# Sheet1.net
KiCad netlist of a schematic drawn in Altium Designer
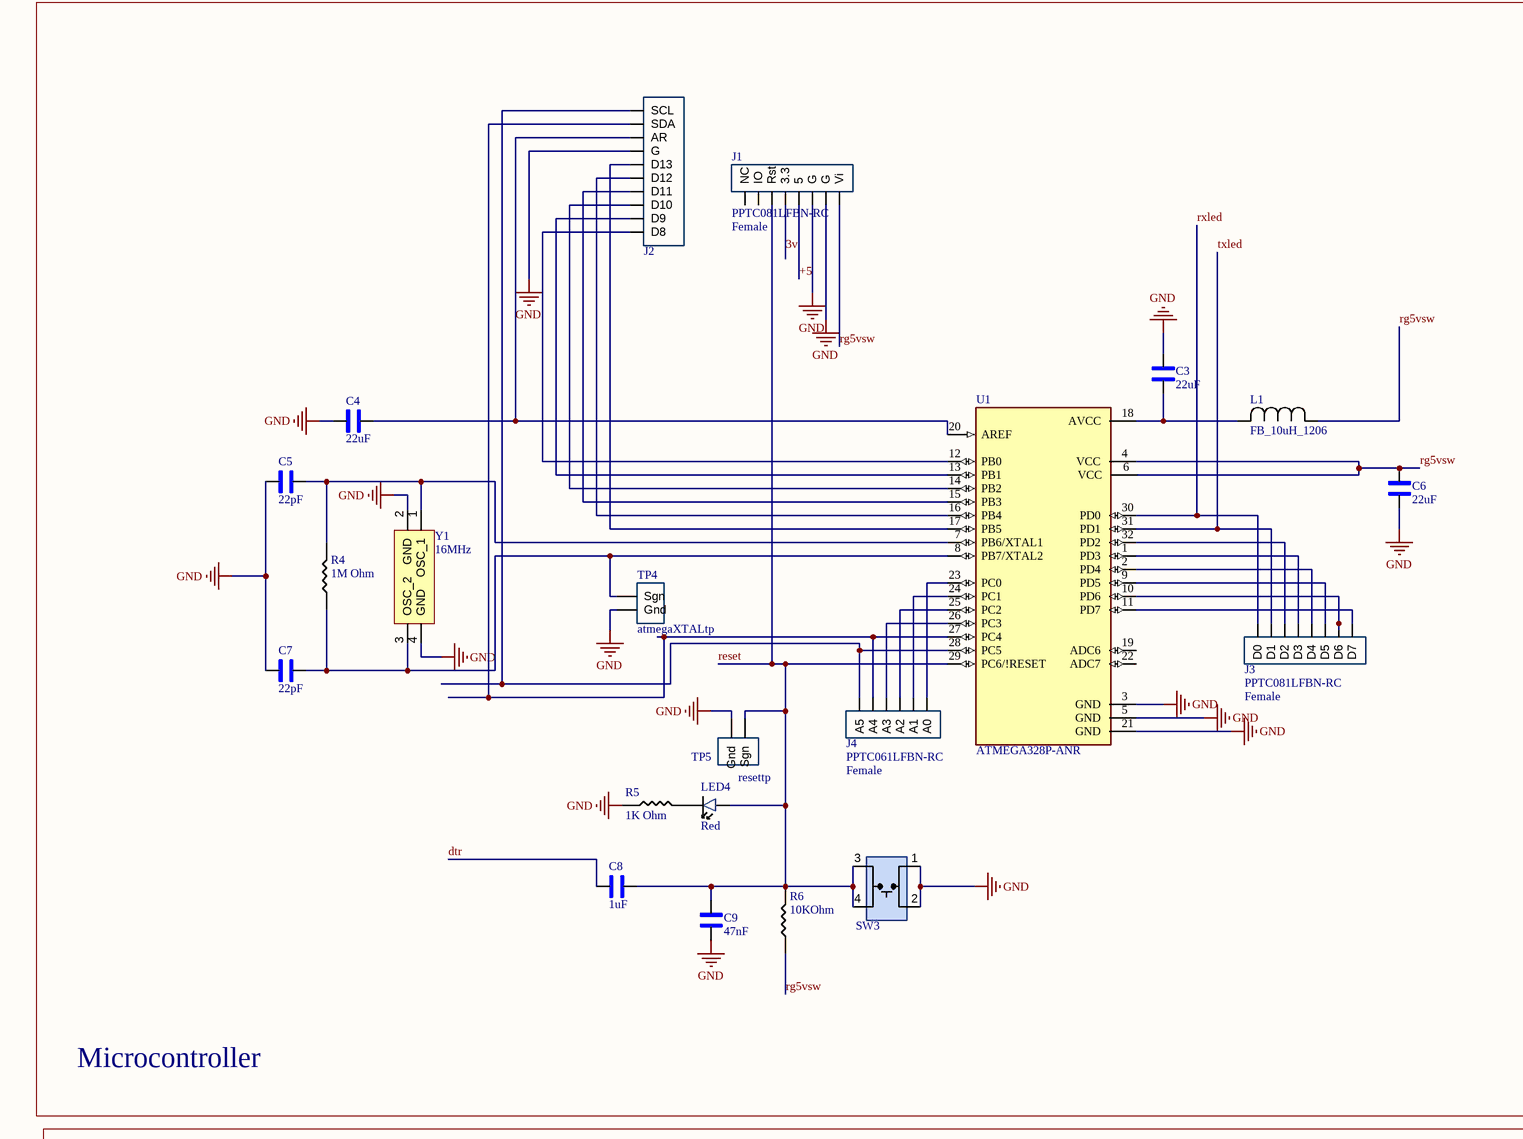
[diagram p0: Sheet1.SchDoc, top left]
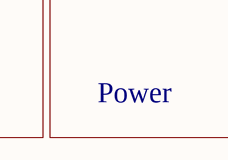
[diagram p1: Sheet1.SchDoc, top middle]
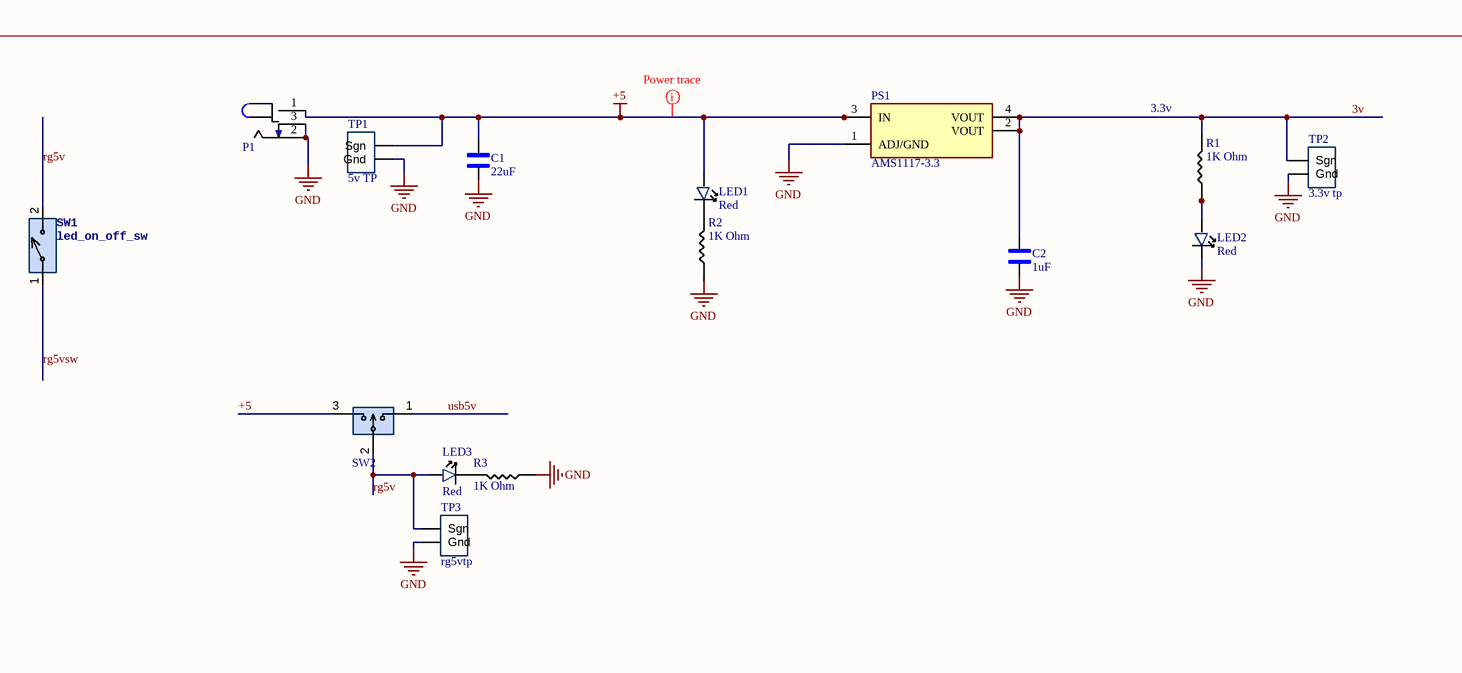
[diagram p2: Sheet1.SchDoc, top right]
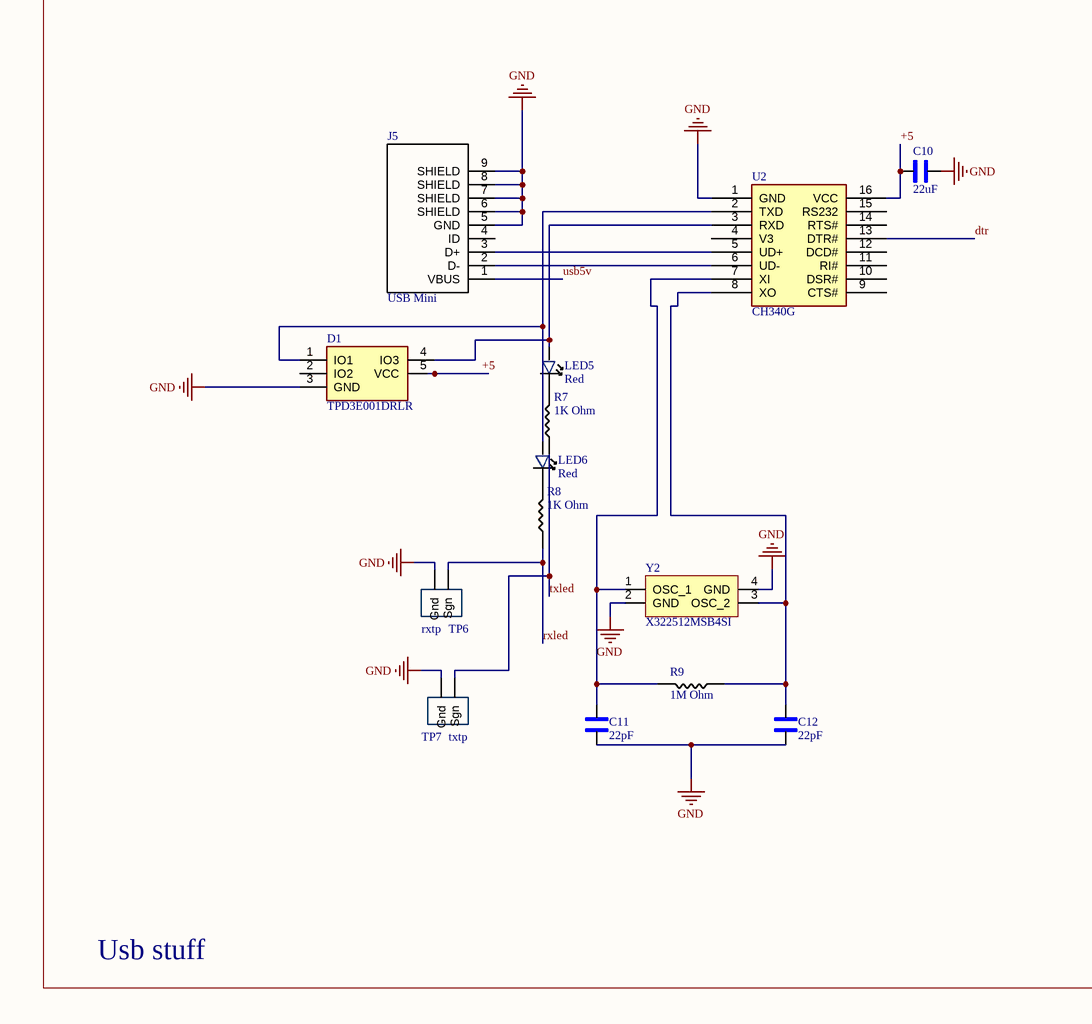
[diagram p3: Sheet1.SchDoc, bottom left]

(export (version "E")
  (design (tool "Eeschema 10.0.6"))
  (components
    (comp (ref "C1")
      (value "22uF")
      (footprint "1206_Passive_Capacitor")
      (description "22uF ±10% 25V X5R 1206 Multilayer Ceramic Capacitors MLCC - SMD/SMT RoHS")
      (fields (field (name "MFR PART #") "CL31A226KAHNNNE") (field (name "LCSC PART#") "C12891"))
      (libsource (lib "ECEN5730Lib_2023_05_DS") (part "C_22uF_1206"))
    )
    (comp (ref "C2")
      (value "1uF")
      (footprint "1206_Passive_Capacitor")
      (description "MULTILAYER CERAMIC CAPACITORS MLCC - SMD/SMT 1UF 50V 1206 ROHS")
      (fields (field (name "MFR PART #") "CL31B105KBHNNNE") (field (name "LCSC PART#") "C1848"))
      (libsource (lib "ECEN5730Lib_2023_05_DS") (part "C_1uF_1206"))
    )
    (comp (ref "C3")
      (value "22uF")
      (footprint "1206_Passive_Capacitor")
      (description "22uF ±10% 25V X5R 1206 Multilayer Ceramic Capacitors MLCC - SMD/SMT RoHS")
      (fields (field (name "MFR PART #") "CL31A226KAHNNNE") (field (name "LCSC PART#") "C12891"))
      (libsource (lib "ECEN5730Lib_2023_05_DS") (part "C_22uF_1206"))
    )
    (comp (ref "C4")
      (value "22uF")
      (footprint "1206_Passive_Capacitor")
      (description "22uF ±10% 25V X5R 1206 Multilayer Ceramic Capacitors MLCC - SMD/SMT RoHS")
      (fields (field (name "MFR PART #") "CL31A226KAHNNNE") (field (name "LCSC PART#") "C12891"))
      (libsource (lib "ECEN5730Lib_2023_05_DS") (part "C_22uF_1206"))
    )
    (comp (ref "C5")
      (value "22pF")
      (footprint "1206_Passive_Capacitor")
      (description "22pF ±5% 1kV C0G 1206 Multilayer Ceramic Capacitors MLCC - SMD/SMT RoHS")
      (fields (field (name "LCSC PART#") "C107174") (field (name "MFR PART #") "CC1206JKNPOCBN220"))
      (libsource (lib "ECEN5730Lib_2023_05_DS") (part "C_22pF_1206"))
    )
    (comp (ref "C6")
      (value "22uF")
      (footprint "1206_Passive_Capacitor")
      (description "22uF ±10% 25V X5R 1206 Multilayer Ceramic Capacitors MLCC - SMD/SMT RoHS")
      (fields (field (name "MFR PART #") "CL31A226KAHNNNE") (field (name "LCSC PART#") "C12891"))
      (libsource (lib "ECEN5730Lib_2023_05_DS") (part "C_22uF_1206"))
    )
    (comp (ref "C7")
      (value "22pF")
      (footprint "1206_Passive_Capacitor")
      (description "22pF ±5% 1kV C0G 1206 Multilayer Ceramic Capacitors MLCC - SMD/SMT RoHS")
      (fields (field (name "LCSC PART#") "C107174") (field (name "MFR PART #") "CC1206JKNPOCBN220"))
      (libsource (lib "ECEN5730Lib_2023_05_DS") (part "C_22pF_1206"))
    )
    (comp (ref "C8")
      (value "1uF")
      (footprint "1206_Passive_Capacitor")
      (description "MULTILAYER CERAMIC CAPACITORS MLCC - SMD/SMT 1UF 50V 1206 ROHS")
      (fields (field (name "MFR PART #") "CL31B105KBHNNNE") (field (name "LCSC PART#") "C1848"))
      (libsource (lib "ECEN5730Lib_2023_05_DS") (part "C_1uF_1206"))
    )
    (comp (ref "C9")
      (value "47nF")
      (footprint "1206_Passive_Capacitor")
      (description "47nF ±5% 50V C0G 1206 Multilayer Ceramic Capacitors MLCC - SMD/SMT RoHS")
      (fields (field (name "LCSC PART#") "C21812") (field (name "MFR PART #") "GRM31M5C1H473JA01L"))
      (libsource (lib "ECEN5730Lib_2023_05_DS") (part "C_47nF_1206"))
    )
    (comp (ref "C10")
      (value "22uF")
      (footprint "1206_Passive_Capacitor")
      (description "22uF ±10% 25V X5R 1206 Multilayer Ceramic Capacitors MLCC - SMD/SMT RoHS")
      (fields (field (name "MFR PART #") "CL31A226KAHNNNE") (field (name "LCSC PART#") "C12891"))
      (libsource (lib "ECEN5730Lib_2023_05_DS") (part "C_22uF_1206"))
    )
    (comp (ref "C11")
      (value "22pF")
      (footprint "1206_Passive_Capacitor")
      (description "22pF ±5% 1kV C0G 1206 Multilayer Ceramic Capacitors MLCC - SMD/SMT RoHS")
      (fields (field (name "LCSC PART#") "C107174") (field (name "MFR PART #") "CC1206JKNPOCBN220"))
      (libsource (lib "ECEN5730Lib_2023_05_DS") (part "C_22pF_1206"))
    )
    (comp (ref "C12")
      (value "22pF")
      (footprint "1206_Passive_Capacitor")
      (description "22pF ±5% 1kV C0G 1206 Multilayer Ceramic Capacitors MLCC - SMD/SMT RoHS")
      (fields (field (name "LCSC PART#") "C107174") (field (name "MFR PART #") "CC1206JKNPOCBN220"))
      (libsource (lib "ECEN5730Lib_2023_05_DS") (part "C_22pF_1206"))
    )
    (comp (ref "D1")
      (value "TPD3E001DRLR")
      (footprint "SOTFL50P160X60-5N:SOTFL50P160X60-5N")
      (description "Low-Capacitance 3-Channel +/-15KV ESD-Protection Array for High-Speed Data Interfaces")
      (fields (field (name "MOUSER PART NUMBER") "595-TPD3E001DRLR"))
      (libsource (lib "TPD3E001DRLR") (part "TPD3E001DRLR"))
    )
    (comp (ref "J1")
      (value "PPTC081LFBN-RC")
      (footprint "8_PIN_ARD-PWR_100MIL")
      (description "8 Position Header Connector 0.100\" (2.54mm) Through Hole Tin")
      (fields (field (name "LCSC PART#") "C27438") (field (name "ALTIUM_VALUE") "Female"))
      (libsource (lib "ECEN5730Lib_2023_05_DS") (part "JF_8_PIN_FEMA_ARD-Pwr"))
    )
    (comp (ref "J2")
      (value "PPTC101LFBN-RC")
      (footprint "10_PIN_ARDUINO_100MIL")
      (description "10 Position Header Connector 0.100\" (2.54mm) Through Hole Tin")
      (fields (field (name "LCSC PART#") "C225507"))
      (libsource (lib "ECEN5730Lib_2023_05_DS") (part "JF_10_PIN_FEMA_ARDUINO"))
    )
    (comp (ref "J3")
      (value "PPTC081LFBN-RC")
      (footprint "8_PIN_ARD-DIG_100MIL")
      (description "8 Position Header Connector 0.100\" (2.54mm) Through Hole Tin")
      (fields (field (name "LCSC PART#") "C27438") (field (name "ALTIUM_VALUE") "Female"))
      (libsource (lib "ECEN5730Lib_2023_05_DS") (part "JF_8_PIN_FEMA_ARD-Dig"))
    )
    (comp (ref "J4")
      (value "PPTC061LFBN-RC")
      (footprint "6_PIN_ARD-Analog_100mil")
      (description "6 Position Header Connector 0.100\" (2.54mm) Through Hole Tin")
      (fields (field (name "LCSC PART#") "C40877") (field (name "ALTIUM_VALUE") "Female"))
      (libsource (lib "ECEN5730Lib_2023_05_DS") (part "JF_6_PIN_FEMA_ARD-Anolog"))
    )
    (comp (ref "J5")
      (value "USB Mini")
      (footprint "USB_MINI_B")
      (description "Through Hole USB Connectors RoHS")
      (fields (field (name "LCSC PART#") "C46398") (field (name "MFR PART #") "920-462A2021D10102"))
      (libsource (lib "ECEN5730Lib_2023_05_DS") (part "J_USB_B_Mini"))
    )
    (comp (ref "L1")
      (value "FB_10uH_1206")
      (footprint "AIML-1206_ABR-M")
      (description "25mA 10uH ±10% 800mΩ 1206  Inductors (SMD) ROHS")
      (fields (field (name "MFR PART #") "CMI321609X100KT") (field (name "LCSC PART#") "C1051"))
      (libsource (lib "ECEN5730Lib_2023_05_DS") (part "FB_10uH_1206"))
    )
    (comp (ref "LED1")
      (value "Red")
      (footprint "LED_1206")
      (description "Red 621~631nm 1206 Light Emitting Diodes (LED) RoHS")
      (fields (field (name "MFR PART #") "15-21/R6C-FQ1R1B/2T") (field (name "LCSC PART#") "C93133"))
      (libsource (lib "ECEN5730Lib_2023_05_DS") (part "LED_RED_1206"))
    )
    (comp (ref "LED2")
      (value "Red")
      (footprint "LED_1206")
      (description "Red 621~631nm 1206 Light Emitting Diodes (LED) RoHS")
      (fields (field (name "MFR PART #") "15-21/R6C-FQ1R1B/2T") (field (name "LCSC PART#") "C93133"))
      (libsource (lib "ECEN5730Lib_2023_05_DS") (part "LED_RED_1206"))
    )
    (comp (ref "LED3")
      (value "Red")
      (footprint "LED_1206")
      (description "Red 621~631nm 1206 Light Emitting Diodes (LED) RoHS")
      (fields (field (name "MFR PART #") "15-21/R6C-FQ1R1B/2T") (field (name "LCSC PART#") "C93133"))
      (libsource (lib "ECEN5730Lib_2023_05_DS") (part "LED_RED_1206"))
    )
    (comp (ref "LED4")
      (value "Red")
      (footprint "LED_1206")
      (description "Red 621~631nm 1206 Light Emitting Diodes (LED) RoHS")
      (fields (field (name "MFR PART #") "15-21/R6C-FQ1R1B/2T") (field (name "LCSC PART#") "C93133"))
      (libsource (lib "ECEN5730Lib_2023_05_DS") (part "LED_RED_1206"))
    )
    (comp (ref "LED5")
      (value "Red")
      (footprint "LED_1206")
      (description "Red 621~631nm 1206 Light Emitting Diodes (LED) RoHS")
      (fields (field (name "MFR PART #") "15-21/R6C-FQ1R1B/2T") (field (name "LCSC PART#") "C93133"))
      (libsource (lib "ECEN5730Lib_2023_05_DS") (part "LED_RED_1206"))
    )
    (comp (ref "LED6")
      (value "Red")
      (footprint "LED_1206")
      (description "Red 621~631nm 1206 Light Emitting Diodes (LED) RoHS")
      (fields (field (name "MFR PART #") "15-21/R6C-FQ1R1B/2T") (field (name "LCSC PART#") "C93133"))
      (libsource (lib "ECEN5730Lib_2023_05_DS") (part "LED_RED_1206"))
    )
    (comp (ref "P1")
      (value "Power Jack")
      (footprint "Power_Jack")
      (description "Power Barrel Connector Jack 2.10mm ID (0.083\"), 5.50mm OD (0.217\") Through Hole, Right Angle")
      (fields (field (name "MFR PART #") "PJ-102A") (field (name "LCSC PART#") "C136744"))
      (libsource (lib "ECEN5730Lib_2023_05_DS") (part "P_Power Jack"))
    )
    (comp (ref "PS1")
      (value "AMS1117-3.3")
      (footprint "LDO")
      (description "LOW DROPOUT REGULATORS(LDO) POSITIVE FIXED 1.3V @ 800MA 15V 3.3V 1A SOT-223 ROHS")
      (fields (field (name "LCSC PART#") "C6186"))
      (libsource (lib "ECEN5730Lib_2023_05_DS") (part "PS_AMS_LDO_3v3"))
    )
    (comp (ref "R1")
      (value "1K Ohm")
      (footprint "1206_Passive_Resitor")
      (description "CHIP RESISTOR - SURFACE MOUNT 1KOHMS ±1% 1/4W 1206 ROHS")
      (fields (field (name "MFR PART #") "RNCP1206FTD1K00CT") (field (name "LCSC PART#") "C4410"))
      (libsource (lib "ECEN5730Lib_2023_05_DS") (part "R_1K_1206"))
    )
    (comp (ref "R2")
      (value "1K Ohm")
      (footprint "1206_Passive_Resitor")
      (description "CHIP RESISTOR - SURFACE MOUNT 1KOHMS ±1% 1/4W 1206 ROHS")
      (fields (field (name "MFR PART #") "RNCP1206FTD1K00CT") (field (name "LCSC PART#") "C4410"))
      (libsource (lib "ECEN5730Lib_2023_05_DS") (part "R_1K_1206"))
    )
    (comp (ref "R3")
      (value "1K Ohm")
      (footprint "1206_Passive_Resitor")
      (description "CHIP RESISTOR - SURFACE MOUNT 1KOHMS ±1% 1/4W 1206 ROHS")
      (fields (field (name "MFR PART #") "RNCP1206FTD1K00CT") (field (name "LCSC PART#") "C4410"))
      (libsource (lib "ECEN5730Lib_2023_05_DS") (part "R_1K_1206"))
    )
    (comp (ref "R4")
      (value "1M Ohm")
      (footprint "1206_Passive_Resitor")
      (description "CHIP RESISTOR - SURFACE MOUNT 1MOHMS ±1% 1/4W 1206 ROHS")
      (fields (field (name "MFR PART #") "RMCF1206JT1M00") (field (name "LCSC PART#") "C17927"))
      (libsource (lib "ECEN5730Lib_2023_05_DS") (part "R_1M_1206"))
    )
    (comp (ref "R5")
      (value "1K Ohm")
      (footprint "1206_Passive_Resitor")
      (description "CHIP RESISTOR - SURFACE MOUNT 1KOHMS ±1% 1/4W 1206 ROHS")
      (fields (field (name "MFR PART #") "RNCP1206FTD1K00CT") (field (name "LCSC PART#") "C4410"))
      (libsource (lib "ECEN5730Lib_2023_05_DS") (part "R_1K_1206"))
    )
    (comp (ref "R6")
      (value "10KOhm")
      (footprint "1206_Passive_Resitor")
      (description "10 kOhms ±5% 0.25W, 1/4W Chip Resistor 1206 (3216 Metric) Automotive AEC-Q200 Thick Film")
      (fields (field (name "MFR PART #") "RMCF1206FT10K0") (field (name "LCSC PART#") "C17902"))
      (libsource (lib "ECEN5730Lib_2023_05_DS") (part "R_10KOhm_1206"))
    )
    (comp (ref "R7")
      (value "1K Ohm")
      (footprint "1206_Passive_Resitor")
      (description "CHIP RESISTOR - SURFACE MOUNT 1KOHMS ±1% 1/4W 1206 ROHS")
      (fields (field (name "MFR PART #") "RNCP1206FTD1K00CT") (field (name "LCSC PART#") "C4410"))
      (libsource (lib "ECEN5730Lib_2023_05_DS") (part "R_1K_1206"))
    )
    (comp (ref "R8")
      (value "1K Ohm")
      (footprint "1206_Passive_Resitor")
      (description "CHIP RESISTOR - SURFACE MOUNT 1KOHMS ±1% 1/4W 1206 ROHS")
      (fields (field (name "MFR PART #") "RNCP1206FTD1K00CT") (field (name "LCSC PART#") "C4410"))
      (libsource (lib "ECEN5730Lib_2023_05_DS") (part "R_1K_1206"))
    )
    (comp (ref "R9")
      (value "1M Ohm")
      (footprint "1206_Passive_Resitor")
      (description "CHIP RESISTOR - SURFACE MOUNT 1MOHMS ±1% 1/4W 1206 ROHS")
      (fields (field (name "MFR PART #") "RMCF1206JT1M00") (field (name "LCSC PART#") "C17927"))
      (libsource (lib "ECEN5730Lib_2023_05_DS") (part "R_1M_1206"))
    )
    (comp (ref "SW1")
      (value "led_on_off_sw")
      (footprint "2Pin-Header-Conn")
      (description "2Pin Header")
      (fields (field (name "LCSC PART#") "C124375"))
      (libsource (lib "ECEN5730Lib_2023_05_DS") (part "SW_2Pin_100mil_Switch"))
    )
    (comp (ref "SW2")
      (value "PREC003SAAN-RC")
      (footprint "3_PIN_100mil")
      (description "Connector Header Through Hole 3 position 0.100\" (2.54mm)")
      (fields (field (name "LCSC PART#") "C49257"))
      (libsource (lib "ECEN5730Lib_2023_05_DS") (part "SW_3Pin_100mil_Switch"))
    )
    (comp (ref "SW3")
      (value "TL3305AF160QG")
      (footprint "Switch_JLC")
      (description "Tactile Switch SPST-NO Top Actuated Surface Mount")
      (fields (field (name "MFR PART #") "KH-4.5X4.5X4.3H-STM") (field (name "LCSC PART#") "C2837550"))
      (libsource (lib "ECEN5730Lib_2023_05_DS") (part "SW_Push_Button_JLC"))
    )
    (comp (ref "TP1")
      (value "5v TP")
      (footprint "TP10x_Probe")
      (description "Test Point 300 mil centers")
      (libsource (lib "ECEN5730Lib_2023_05_DS") (part "TP_10x_Probe"))
    )
    (comp (ref "TP2")
      (value "3.3v tp")
      (footprint "TP10x_Probe")
      (description "Test Point 300 mil centers")
      (libsource (lib "") (part "TP_10x_Probe_1"))
    )
    (comp (ref "TP3")
      (value "rg5vtp")
      (footprint "TP10x_Probe")
      (description "Test Point 300 mil centers")
      (libsource (lib "") (part "TP_10x_Probe_1"))
    )
    (comp (ref "TP4")
      (value "atmegaXTALtp")
      (footprint "TP10x_Probe")
      (description "Test Point 300 mil centers")
      (libsource (lib "") (part "TP_10x_Probe_1"))
    )
    (comp (ref "TP5")
      (value "resettp")
      (footprint "TP10x_Probe")
      (description "Test Point 300 mil centers")
      (libsource (lib "ECEN5730Lib_2023_05_DS") (part "TP_10x_Probe"))
    )
    (comp (ref "TP6")
      (value "rxtp")
      (footprint "TP10x_Probe")
      (description "Test Point 300 mil centers")
      (libsource (lib "ECEN5730Lib_2023_05_DS") (part "TP_10x_Probe"))
    )
    (comp (ref "TP7")
      (value "txtp")
      (footprint "TP10x_Probe")
      (description "Test Point 300 mil centers")
      (libsource (lib "ECEN5730Lib_2023_05_DS") (part "TP_10x_Probe"))
    )
    (comp (ref "U1")
      (value "ATMEGA328P-ANR")
      (footprint "ATMega328P")
      (description "AVR AVR® ATmega Microcontroller IC 8-Bit 20MHz 32KB (16K x 16) FLASH 32-TQFP (7x7)")
      (fields (field (name "MFR PART #") "ATMEGA328P-AU") (field (name "LCSC PART#") "C14877"))
      (libsource (lib "ECEN5730Lib_2023_05_DS") (part "U_ATMega328P"))
    )
    (comp (ref "U2")
      (value "CH340G")
      (footprint "USB to serial")
      (description "Transceiver USB 2.0 2Mbps SOP-16_150mil USB ICs RoHS")
      (fields (field (name "LCSC PART#") "C14267"))
      (libsource (lib "ECEN5730Lib_2023_05_DS") (part "U_USBtoSerial"))
    )
    (comp (ref "Y1")
      (value "16MHz")
      (footprint "Crystal resonator")
      (description "±10ppm 16000000Hz -40℃~85℃ 贴片无源晶振 60Ω 9pF SMD3225-4P Crystals ROHS")
      (fields (field (name "LCSC PART#") "C13738") (field (name "MFR PART #") "X322516MLB4SI"))
      (libsource (lib "ECEN5730Lib_2023_05_DS") (part "X_16Mhz_Res"))
    )
    (comp (ref "Y2")
      (value "X322512MSB4SI")
      (footprint "Crystal resonator")
      (description "SMD Crystal Resonators 12MHz ±10ppm SMD-3225_4P RoHS")
      (fields (field (name "LCSC PART#") "C9002"))
      (libsource (lib "ECEN5730Lib_2023_05_DS") (part "X_12MHz_Res"))
    )
  )
  (nets
    (net (code "1") (name "+5") (class "Default")
      (node (ref "C1") (pin "2") (pinfunction "2_2") (pintype "passive"))
      (node (ref "C10") (pin "1") (pinfunction "1_1") (pintype "passive"))
      (node (ref "D1") (pin "5") (pinfunction "VCC_5") (pintype "passive"))
      (node (ref "J1") (pin "5") (pinfunction "5_5") (pintype "passive"))
      (node (ref "LED1") (pin "1") (pinfunction "1_1") (pintype "passive"))
      (node (ref "P1") (pin "1") (pinfunction "1_1") (pintype "power_in"))
      (node (ref "PS1") (pin "3") (pinfunction "IN_3") (pintype "power_in"))
      (node (ref "SW2") (pin "3") (pinfunction "3_3") (pintype "passive"))
      (node (ref "TP1") (pin "1") (pinfunction "Sgn_1") (pintype "passive"))
      (node (ref "U2") (pin "16") (pinfunction "VCC_16") (pintype "passive"))
    )
    (net (code "2") (name "/3v") (class "Default")
      (node (ref "C2") (pin "2") (pinfunction "2_2") (pintype "passive"))
      (node (ref "J1") (pin "4") (pinfunction "3.3_4") (pintype "passive"))
      (node (ref "PS1") (pin "2") (pinfunction "VOUT_2") (pintype "power_in"))
      (node (ref "PS1") (pin "4") (pinfunction "VOUT_4") (pintype "power_in"))
      (node (ref "R1") (pin "2") (pinfunction "2_2") (pintype "passive"))
      (node (ref "TP2") (pin "1") (pinfunction "Sgn_1") (pintype "passive"))
    )
    (net (code "3") (name "/dtr") (class "Default")
      (node (ref "C8") (pin "1") (pinfunction "1_1") (pintype "passive"))
      (node (ref "U2") (pin "13") (pinfunction "DTR#_13") (pintype "passive"))
    )
    (net (code "4") (name "/reset") (class "Default")
      (node (ref "C8") (pin "2") (pinfunction "2_2") (pintype "passive"))
      (node (ref "C9") (pin "2") (pinfunction "2_2") (pintype "passive"))
      (node (ref "J1") (pin "3") (pinfunction "Rst_3") (pintype "passive"))
      (node (ref "LED4") (pin "1") (pinfunction "1_1") (pintype "passive"))
      (node (ref "R6") (pin "2") (pinfunction "2_2") (pintype "passive"))
      (node (ref "SW3") (pin "3") (pinfunction "3_3") (pintype "passive"))
      (node (ref "SW3") (pin "4") (pinfunction "4_4") (pintype "passive"))
      (node (ref "TP5") (pin "1") (pinfunction "Sgn_1") (pintype "passive"))
      (node (ref "U1") (pin "29") (pinfunction "PC6/!RESET_29") (pintype "bidirectional"))
    )
    (net (code "5") (name "/rg5v") (class "Default")
      (node (ref "LED3") (pin "1") (pinfunction "1_1") (pintype "passive"))
      (node (ref "SW1") (pin "2") (pinfunction "2_2") (pintype "passive"))
      (node (ref "SW2") (pin "2") (pinfunction "2_2") (pintype "passive"))
      (node (ref "TP3") (pin "1") (pinfunction "Sgn_1") (pintype "passive"))
    )
    (net (code "6") (name "/rg5vsw") (class "Default")
      (node (ref "C6") (pin "2") (pinfunction "2_2") (pintype "passive"))
      (node (ref "J1") (pin "8") (pinfunction "Vi_8") (pintype "passive"))
      (node (ref "L1") (pin "1") (pinfunction "1_1") (pintype "passive"))
      (node (ref "R6") (pin "1") (pinfunction "1_1") (pintype "passive"))
      (node (ref "SW1") (pin "1") (pinfunction "1_1") (pintype "passive"))
      (node (ref "U1") (pin "4") (pinfunction "VCC_4") (pintype "power_in"))
      (node (ref "U1") (pin "6") (pinfunction "VCC_6") (pintype "power_in"))
    )
    (net (code "7") (name "/rxled") (class "Default")
      (node (ref "J3") (pin "8") (pinfunction "D0_8") (pintype "passive"))
      (node (ref "R8") (pin "1") (pinfunction "1_1") (pintype "passive"))
      (node (ref "TP6") (pin "1") (pinfunction "Sgn_1") (pintype "passive"))
      (node (ref "U1") (pin "30") (pinfunction "PD0_30") (pintype "bidirectional"))
    )
    (net (code "8") (name "/txled") (class "Default")
      (node (ref "J3") (pin "7") (pinfunction "D1_7") (pintype "passive"))
      (node (ref "R7") (pin "1") (pinfunction "1_1") (pintype "passive"))
      (node (ref "TP7") (pin "1") (pinfunction "Sgn_1") (pintype "passive"))
      (node (ref "U1") (pin "31") (pinfunction "PD1_31") (pintype "bidirectional"))
    )
    (net (code "9") (name "/usb5v") (class "Default")
      (node (ref "J5") (pin "1") (pinfunction "VBUS_1") (pintype "passive"))
      (node (ref "SW2") (pin "1") (pinfunction "1_1") (pintype "passive"))
    )
    (net (code "10") (name "GND") (class "Default")
      (node (ref "C1") (pin "1") (pinfunction "1_1") (pintype "passive"))
      (node (ref "C10") (pin "2") (pinfunction "2_2") (pintype "passive"))
      (node (ref "C11") (pin "1") (pinfunction "1_1") (pintype "passive"))
      (node (ref "C12") (pin "1") (pinfunction "1_1") (pintype "passive"))
      (node (ref "C2") (pin "1") (pinfunction "1_1") (pintype "passive"))
      (node (ref "C3") (pin "2") (pinfunction "2_2") (pintype "passive"))
      (node (ref "C4") (pin "2") (pinfunction "2_2") (pintype "passive"))
      (node (ref "C5") (pin "1") (pinfunction "1_1") (pintype "passive"))
      (node (ref "C6") (pin "1") (pinfunction "1_1") (pintype "passive"))
      (node (ref "C7") (pin "1") (pinfunction "1_1") (pintype "passive"))
      (node (ref "C9") (pin "1") (pinfunction "1_1") (pintype "passive"))
      (node (ref "D1") (pin "3") (pinfunction "GND_3") (pintype "passive"))
      (node (ref "J1") (pin "6") (pinfunction "G_6") (pintype "passive"))
      (node (ref "J1") (pin "7") (pinfunction "G_7") (pintype "passive"))
      (node (ref "J2") (pin "4") (pinfunction "G_4") (pintype "passive"))
      (node (ref "J5") (pin "5") (pinfunction "GND_5") (pintype "passive"))
      (node (ref "J5") (pin "6") (pinfunction "SHIELD_6") (pintype "passive"))
      (node (ref "J5") (pin "7") (pinfunction "SHIELD_7") (pintype "passive"))
      (node (ref "J5") (pin "8") (pinfunction "SHIELD_8") (pintype "passive"))
      (node (ref "J5") (pin "9") (pinfunction "SHIELD_9") (pintype "passive"))
      (node (ref "LED2") (pin "2") (pinfunction "2_2") (pintype "passive"))
      (node (ref "P1") (pin "2") (pinfunction "2_2") (pintype "power_in"))
      (node (ref "P1") (pin "3") (pinfunction "3_3") (pintype "power_in"))
      (node (ref "PS1") (pin "1") (pinfunction "ADJ/GND_1") (pintype "passive"))
      (node (ref "R2") (pin "1") (pinfunction "1_1") (pintype "passive"))
      (node (ref "R3") (pin "1") (pinfunction "1_1") (pintype "passive"))
      (node (ref "R5") (pin "1") (pinfunction "1_1") (pintype "passive"))
      (node (ref "SW3") (pin "1") (pinfunction "1_1") (pintype "passive"))
      (node (ref "SW3") (pin "2") (pinfunction "2_2") (pintype "passive"))
      (node (ref "TP1") (pin "2") (pinfunction "Gnd_2") (pintype "passive"))
      (node (ref "TP2") (pin "2") (pinfunction "Gnd_2") (pintype "passive"))
      (node (ref "TP3") (pin "2") (pinfunction "Gnd_2") (pintype "passive"))
      (node (ref "TP4") (pin "2") (pinfunction "Gnd_2") (pintype "passive"))
      (node (ref "TP5") (pin "2") (pinfunction "Gnd_2") (pintype "passive"))
      (node (ref "TP6") (pin "2") (pinfunction "Gnd_2") (pintype "passive"))
      (node (ref "TP7") (pin "2") (pinfunction "Gnd_2") (pintype "passive"))
      (node (ref "U1") (pin "21") (pinfunction "GND_21") (pintype "power_in"))
      (node (ref "U1") (pin "3") (pinfunction "GND_3") (pintype "power_in"))
      (node (ref "U1") (pin "5") (pinfunction "GND_5") (pintype "power_in"))
      (node (ref "U2") (pin "1") (pinfunction "GND_1") (pintype "passive"))
      (node (ref "Y1") (pin "2") (pinfunction "GND_2") (pintype "passive"))
      (node (ref "Y1") (pin "4") (pinfunction "GND_4") (pintype "passive"))
      (node (ref "Y2") (pin "2") (pinfunction "GND_2") (pintype "passive"))
      (node (ref "Y2") (pin "4") (pinfunction "GND_4") (pintype "passive"))
    )
    (net (code "11") (name "Net-(D1-IO1)") (class "Default")
      (node (ref "D1") (pin "1") (pinfunction "IO1_1") (pintype "passive"))
      (node (ref "LED6") (pin "1") (pinfunction "1_1") (pintype "passive"))
      (node (ref "U2") (pin "2") (pinfunction "TXD_2") (pintype "passive"))
    )
    (net (code "12") (name "Net-(D1-IO3)") (class "Default")
      (node (ref "D1") (pin "4") (pinfunction "IO3_4") (pintype "passive"))
      (node (ref "LED5") (pin "1") (pinfunction "1_1") (pintype "passive"))
      (node (ref "U2") (pin "3") (pinfunction "RXD_3") (pintype "passive"))
    )
    (net (code "13") (name "Net-(J2-AR)") (class "Default")
      (node (ref "C4") (pin "1") (pinfunction "1_1") (pintype "passive"))
      (node (ref "J2") (pin "3") (pinfunction "AR_3") (pintype "passive"))
      (node (ref "U1") (pin "20") (pinfunction "AREF_20") (pintype "input"))
    )
    (net (code "14") (name "Net-(J2-D8)") (class "Default")
      (node (ref "J2") (pin "10") (pinfunction "D8_10") (pintype "passive"))
      (node (ref "U1") (pin "12") (pinfunction "PB0_12") (pintype "bidirectional"))
    )
    (net (code "15") (name "Net-(J2-D9)") (class "Default")
      (node (ref "J2") (pin "9") (pinfunction "D9_9") (pintype "passive"))
      (node (ref "U1") (pin "13") (pinfunction "PB1_13") (pintype "bidirectional"))
    )
    (net (code "16") (name "Net-(J2-D10)") (class "Default")
      (node (ref "J2") (pin "8") (pinfunction "D10_8") (pintype "passive"))
      (node (ref "U1") (pin "14") (pinfunction "PB2_14") (pintype "bidirectional"))
    )
    (net (code "17") (name "Net-(J2-D11)") (class "Default")
      (node (ref "J2") (pin "7") (pinfunction "D11_7") (pintype "passive"))
      (node (ref "U1") (pin "15") (pinfunction "PB3_15") (pintype "bidirectional"))
    )
    (net (code "18") (name "Net-(J2-D12)") (class "Default")
      (node (ref "J2") (pin "6") (pinfunction "D12_6") (pintype "passive"))
      (node (ref "U1") (pin "16") (pinfunction "PB4_16") (pintype "bidirectional"))
    )
    (net (code "19") (name "Net-(J2-D13)") (class "Default")
      (node (ref "J2") (pin "5") (pinfunction "D13_5") (pintype "passive"))
      (node (ref "U1") (pin "17") (pinfunction "PB5_17") (pintype "bidirectional"))
    )
    (net (code "20") (name "Net-(J2-SCL)") (class "Default")
      (node (ref "J2") (pin "1") (pinfunction "SCL_1") (pintype "passive"))
      (node (ref "J4") (pin "6") (pinfunction "A5_6") (pintype "passive"))
      (node (ref "U1") (pin "28") (pinfunction "PC5_28") (pintype "bidirectional"))
    )
    (net (code "21") (name "Net-(J2-SDA)") (class "Default")
      (node (ref "J2") (pin "2") (pinfunction "SDA_2") (pintype "passive"))
      (node (ref "J4") (pin "5") (pinfunction "A4_5") (pintype "passive"))
      (node (ref "U1") (pin "27") (pinfunction "PC4_27") (pintype "bidirectional"))
    )
    (net (code "22") (name "Net-(J3-D2)") (class "Default")
      (node (ref "J3") (pin "6") (pinfunction "D2_6") (pintype "passive"))
      (node (ref "U1") (pin "32") (pinfunction "PD2_32") (pintype "bidirectional"))
    )
    (net (code "23") (name "Net-(J3-D3)") (class "Default")
      (node (ref "J3") (pin "5") (pinfunction "D3_5") (pintype "passive"))
      (node (ref "U1") (pin "1") (pinfunction "PD3_1") (pintype "bidirectional"))
    )
    (net (code "24") (name "Net-(J3-D4)") (class "Default")
      (node (ref "J3") (pin "4") (pinfunction "D4_4") (pintype "passive"))
      (node (ref "U1") (pin "2") (pinfunction "PD4_2") (pintype "bidirectional"))
    )
    (net (code "25") (name "Net-(J3-D5)") (class "Default")
      (node (ref "J3") (pin "3") (pinfunction "D5_3") (pintype "passive"))
      (node (ref "U1") (pin "9") (pinfunction "PD5_9") (pintype "bidirectional"))
    )
    (net (code "26") (name "Net-(J3-D6)") (class "Default")
      (node (ref "J3") (pin "2") (pinfunction "D6_2") (pintype "passive"))
      (node (ref "U1") (pin "10") (pinfunction "PD6_10") (pintype "bidirectional"))
    )
    (net (code "27") (name "Net-(J3-D7)") (class "Default")
      (node (ref "J3") (pin "1") (pinfunction "D7_1") (pintype "passive"))
      (node (ref "U1") (pin "11") (pinfunction "PD7_11") (pintype "bidirectional"))
    )
    (net (code "28") (name "Net-(J4-A0)") (class "Default")
      (node (ref "J4") (pin "1") (pinfunction "A0_1") (pintype "passive"))
      (node (ref "U1") (pin "23") (pinfunction "PC0_23") (pintype "bidirectional"))
    )
    (net (code "29") (name "Net-(J4-A1)") (class "Default")
      (node (ref "J4") (pin "2") (pinfunction "A1_2") (pintype "passive"))
      (node (ref "U1") (pin "24") (pinfunction "PC1_24") (pintype "bidirectional"))
    )
    (net (code "30") (name "Net-(J4-A2)") (class "Default")
      (node (ref "J4") (pin "3") (pinfunction "A2_3") (pintype "passive"))
      (node (ref "U1") (pin "25") (pinfunction "PC2_25") (pintype "bidirectional"))
    )
    (net (code "31") (name "Net-(J4-A3)") (class "Default")
      (node (ref "J4") (pin "4") (pinfunction "A3_4") (pintype "passive"))
      (node (ref "U1") (pin "26") (pinfunction "PC3_26") (pintype "bidirectional"))
    )
    (net (code "32") (name "Net-(J5-D+)") (class "Default")
      (node (ref "J5") (pin "3") (pinfunction "D+_3") (pintype "passive"))
      (node (ref "U2") (pin "5") (pinfunction "UD+_5") (pintype "passive"))
    )
    (net (code "33") (name "Net-(J5-D-)") (class "Default")
      (node (ref "J5") (pin "2") (pinfunction "D-_2") (pintype "passive"))
      (node (ref "U2") (pin "6") (pinfunction "UD-_6") (pintype "passive"))
    )
    (net (code "34") (name "Net-(LED1-Pad2)") (class "Default")
      (node (ref "LED1") (pin "2") (pinfunction "2_2") (pintype "passive"))
      (node (ref "R2") (pin "2") (pinfunction "2_2") (pintype "passive"))
    )
    (net (code "35") (name "Net-(LED2-Pad1)") (class "Default")
      (node (ref "LED2") (pin "1") (pinfunction "1_1") (pintype "passive"))
      (node (ref "R1") (pin "1") (pinfunction "1_1") (pintype "passive"))
    )
    (net (code "36") (name "Net-(LED3-Pad2)") (class "Default")
      (node (ref "LED3") (pin "2") (pinfunction "2_2") (pintype "passive"))
      (node (ref "R3") (pin "2") (pinfunction "2_2") (pintype "passive"))
    )
    (net (code "37") (name "Net-(LED4-Pad2)") (class "Default")
      (node (ref "LED4") (pin "2") (pinfunction "2_2") (pintype "passive"))
      (node (ref "R5") (pin "2") (pinfunction "2_2") (pintype "passive"))
    )
    (net (code "38") (name "Net-(LED5-Pad2)") (class "Default")
      (node (ref "LED5") (pin "2") (pinfunction "2_2") (pintype "passive"))
      (node (ref "R7") (pin "2") (pinfunction "2_2") (pintype "passive"))
    )
    (net (code "39") (name "Net-(LED6-Pad2)") (class "Default")
      (node (ref "LED6") (pin "2") (pinfunction "2_2") (pintype "passive"))
      (node (ref "R8") (pin "2") (pinfunction "2_2") (pintype "passive"))
    )
    (net (code "40") (name "Net-(TP4-Sgn)") (class "Default")
      (node (ref "C7") (pin "2") (pinfunction "2_2") (pintype "passive"))
      (node (ref "R4") (pin "1") (pinfunction "1_1") (pintype "passive"))
      (node (ref "TP4") (pin "1") (pinfunction "Sgn_1") (pintype "passive"))
      (node (ref "U1") (pin "8") (pinfunction "PB7/XTAL2_8") (pintype "bidirectional"))
      (node (ref "Y1") (pin "3") (pinfunction "OSC_2_3") (pintype "passive"))
    )
    (net (code "41") (name "Net-(U1-AVCC)") (class "Default")
      (node (ref "C3") (pin "1") (pinfunction "1_1") (pintype "passive"))
      (node (ref "L1") (pin "2") (pinfunction "2_2") (pintype "passive"))
      (node (ref "U1") (pin "18") (pinfunction "AVCC_18") (pintype "power_in"))
    )
    (net (code "42") (name "Net-(U1-PB6{slash}XTAL1)") (class "Default")
      (node (ref "C5") (pin "2") (pinfunction "2_2") (pintype "passive"))
      (node (ref "R4") (pin "2") (pinfunction "2_2") (pintype "passive"))
      (node (ref "U1") (pin "7") (pinfunction "PB6/XTAL1_7") (pintype "bidirectional"))
      (node (ref "Y1") (pin "1") (pinfunction "OSC_1_1") (pintype "passive"))
    )
    (net (code "43") (name "Net-(U2-XI)") (class "Default")
      (node (ref "C11") (pin "2") (pinfunction "2_2") (pintype "passive"))
      (node (ref "R9") (pin "2") (pinfunction "2_2") (pintype "passive"))
      (node (ref "U2") (pin "7") (pinfunction "XI_7") (pintype "passive"))
      (node (ref "Y2") (pin "1") (pinfunction "OSC_1_1") (pintype "passive"))
    )
    (net (code "44") (name "Net-(U2-XO)") (class "Default")
      (node (ref "C12") (pin "2") (pinfunction "2_2") (pintype "passive"))
      (node (ref "R9") (pin "1") (pinfunction "1_1") (pintype "passive"))
      (node (ref "U2") (pin "8") (pinfunction "XO_8") (pintype "passive"))
      (node (ref "Y2") (pin "3") (pinfunction "OSC_2_3") (pintype "passive"))
    )
    (net (code "45") (name "unconnected-(D1-IO2-Pad2)") (class "Default")
      (node (ref "D1") (pin "2") (pinfunction "IO2_2") (pintype "passive"))
    )
    (net (code "46") (name "unconnected-(J1-IO-Pad2)") (class "Default")
      (node (ref "J1") (pin "2") (pinfunction "IO_2") (pintype "passive"))
    )
    (net (code "47") (name "unconnected-(J1-NC-Pad1)") (class "Default")
      (node (ref "J1") (pin "1") (pinfunction "NC_1") (pintype "passive"))
    )
    (net (code "48") (name "unconnected-(J5-ID-Pad4)") (class "Default")
      (node (ref "J5") (pin "4") (pinfunction "ID_4") (pintype "passive"))
    )
    (net (code "49") (name "unconnected-(U1-ADC6-Pad19)") (class "Default")
      (node (ref "U1") (pin "19") (pinfunction "ADC6_19") (pintype "bidirectional"))
    )
    (net (code "50") (name "unconnected-(U1-ADC7-Pad22)") (class "Default")
      (node (ref "U1") (pin "22") (pinfunction "ADC7_22") (pintype "bidirectional"))
    )
    (net (code "51") (name "unconnected-(U2-CTS#-Pad9)") (class "Default")
      (node (ref "U2") (pin "9") (pinfunction "CTS#_9") (pintype "passive"))
    )
    (net (code "52") (name "unconnected-(U2-DCD#-Pad12)") (class "Default")
      (node (ref "U2") (pin "12") (pinfunction "DCD#_12") (pintype "passive"))
    )
    (net (code "53") (name "unconnected-(U2-DSR#-Pad10)") (class "Default")
      (node (ref "U2") (pin "10") (pinfunction "DSR#_10") (pintype "passive"))
    )
    (net (code "54") (name "unconnected-(U2-RI#-Pad11)") (class "Default")
      (node (ref "U2") (pin "11") (pinfunction "RI#_11") (pintype "passive"))
    )
    (net (code "55") (name "unconnected-(U2-RS232-Pad15)") (class "Default")
      (node (ref "U2") (pin "15") (pinfunction "RS232_15") (pintype "passive"))
    )
    (net (code "56") (name "unconnected-(U2-RTS#-Pad14)") (class "Default")
      (node (ref "U2") (pin "14") (pinfunction "RTS#_14") (pintype "passive"))
    )
    (net (code "57") (name "unconnected-(U2-V3-Pad4)") (class "Default")
      (node (ref "U2") (pin "4") (pinfunction "V3_4") (pintype "passive"))
    )
  )
)
